# ECUs.net
KiCad netlist of a schematic drawn in EasyEDA
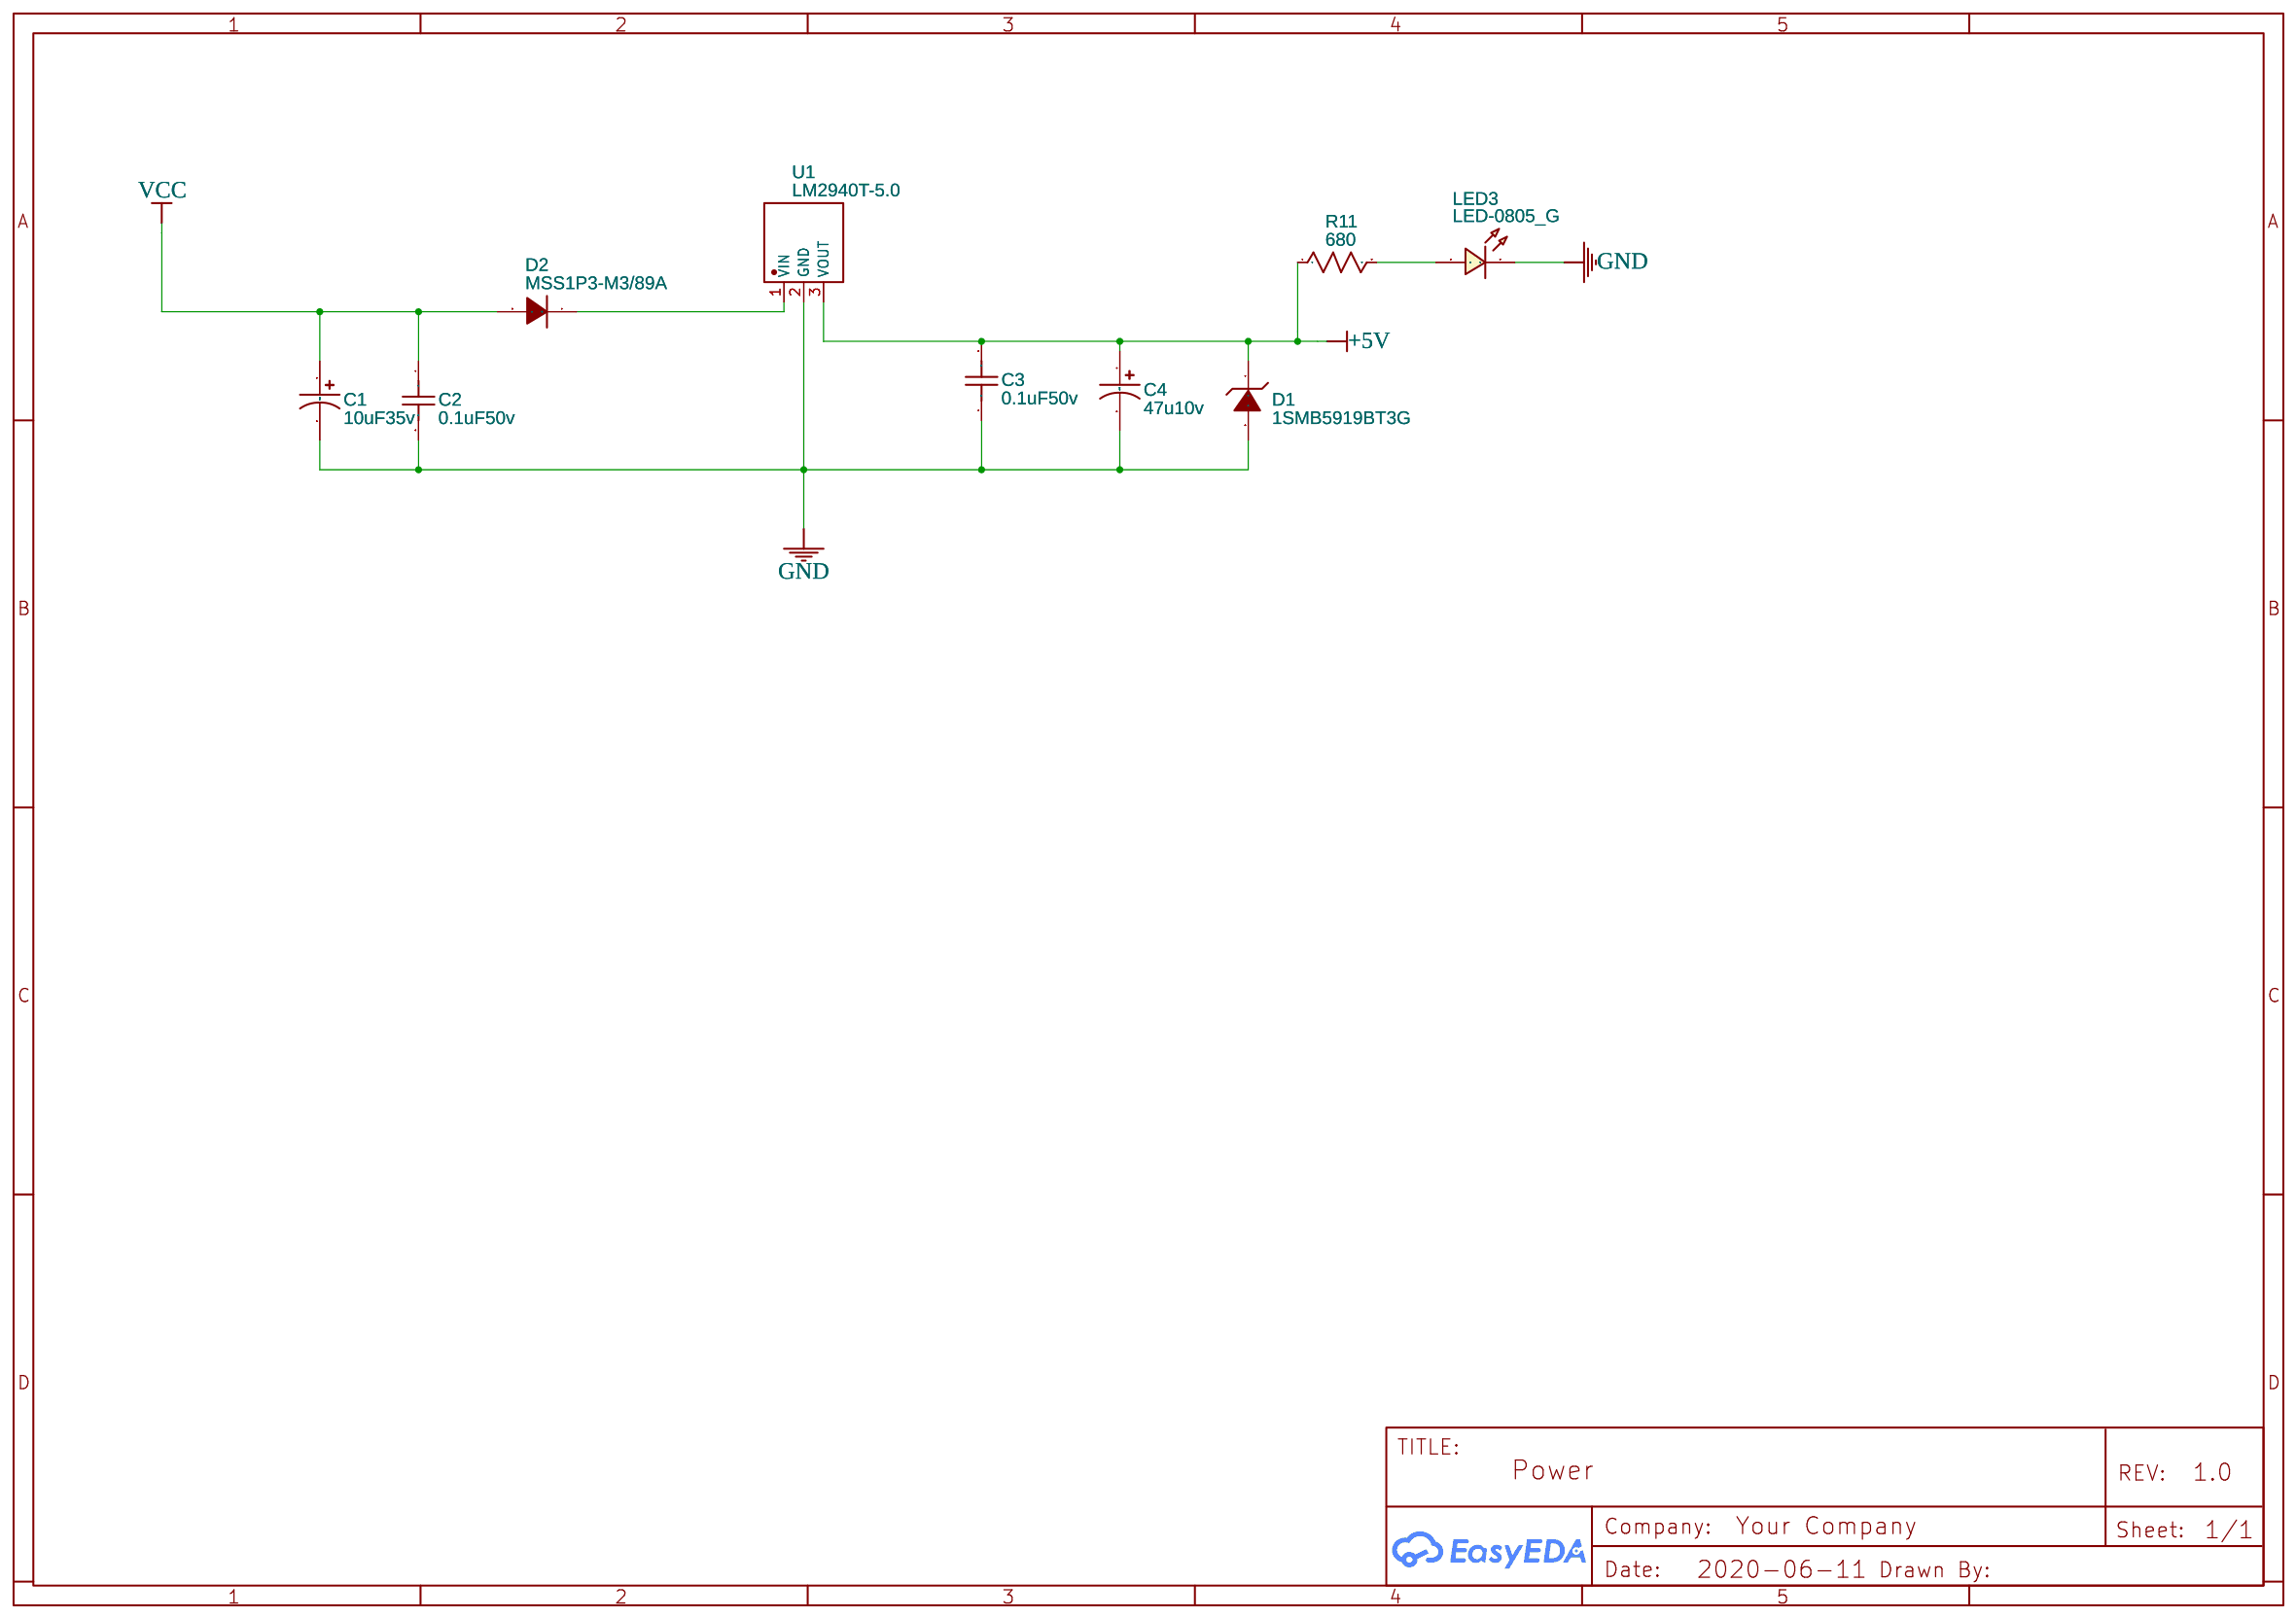
[diagram p0: power]
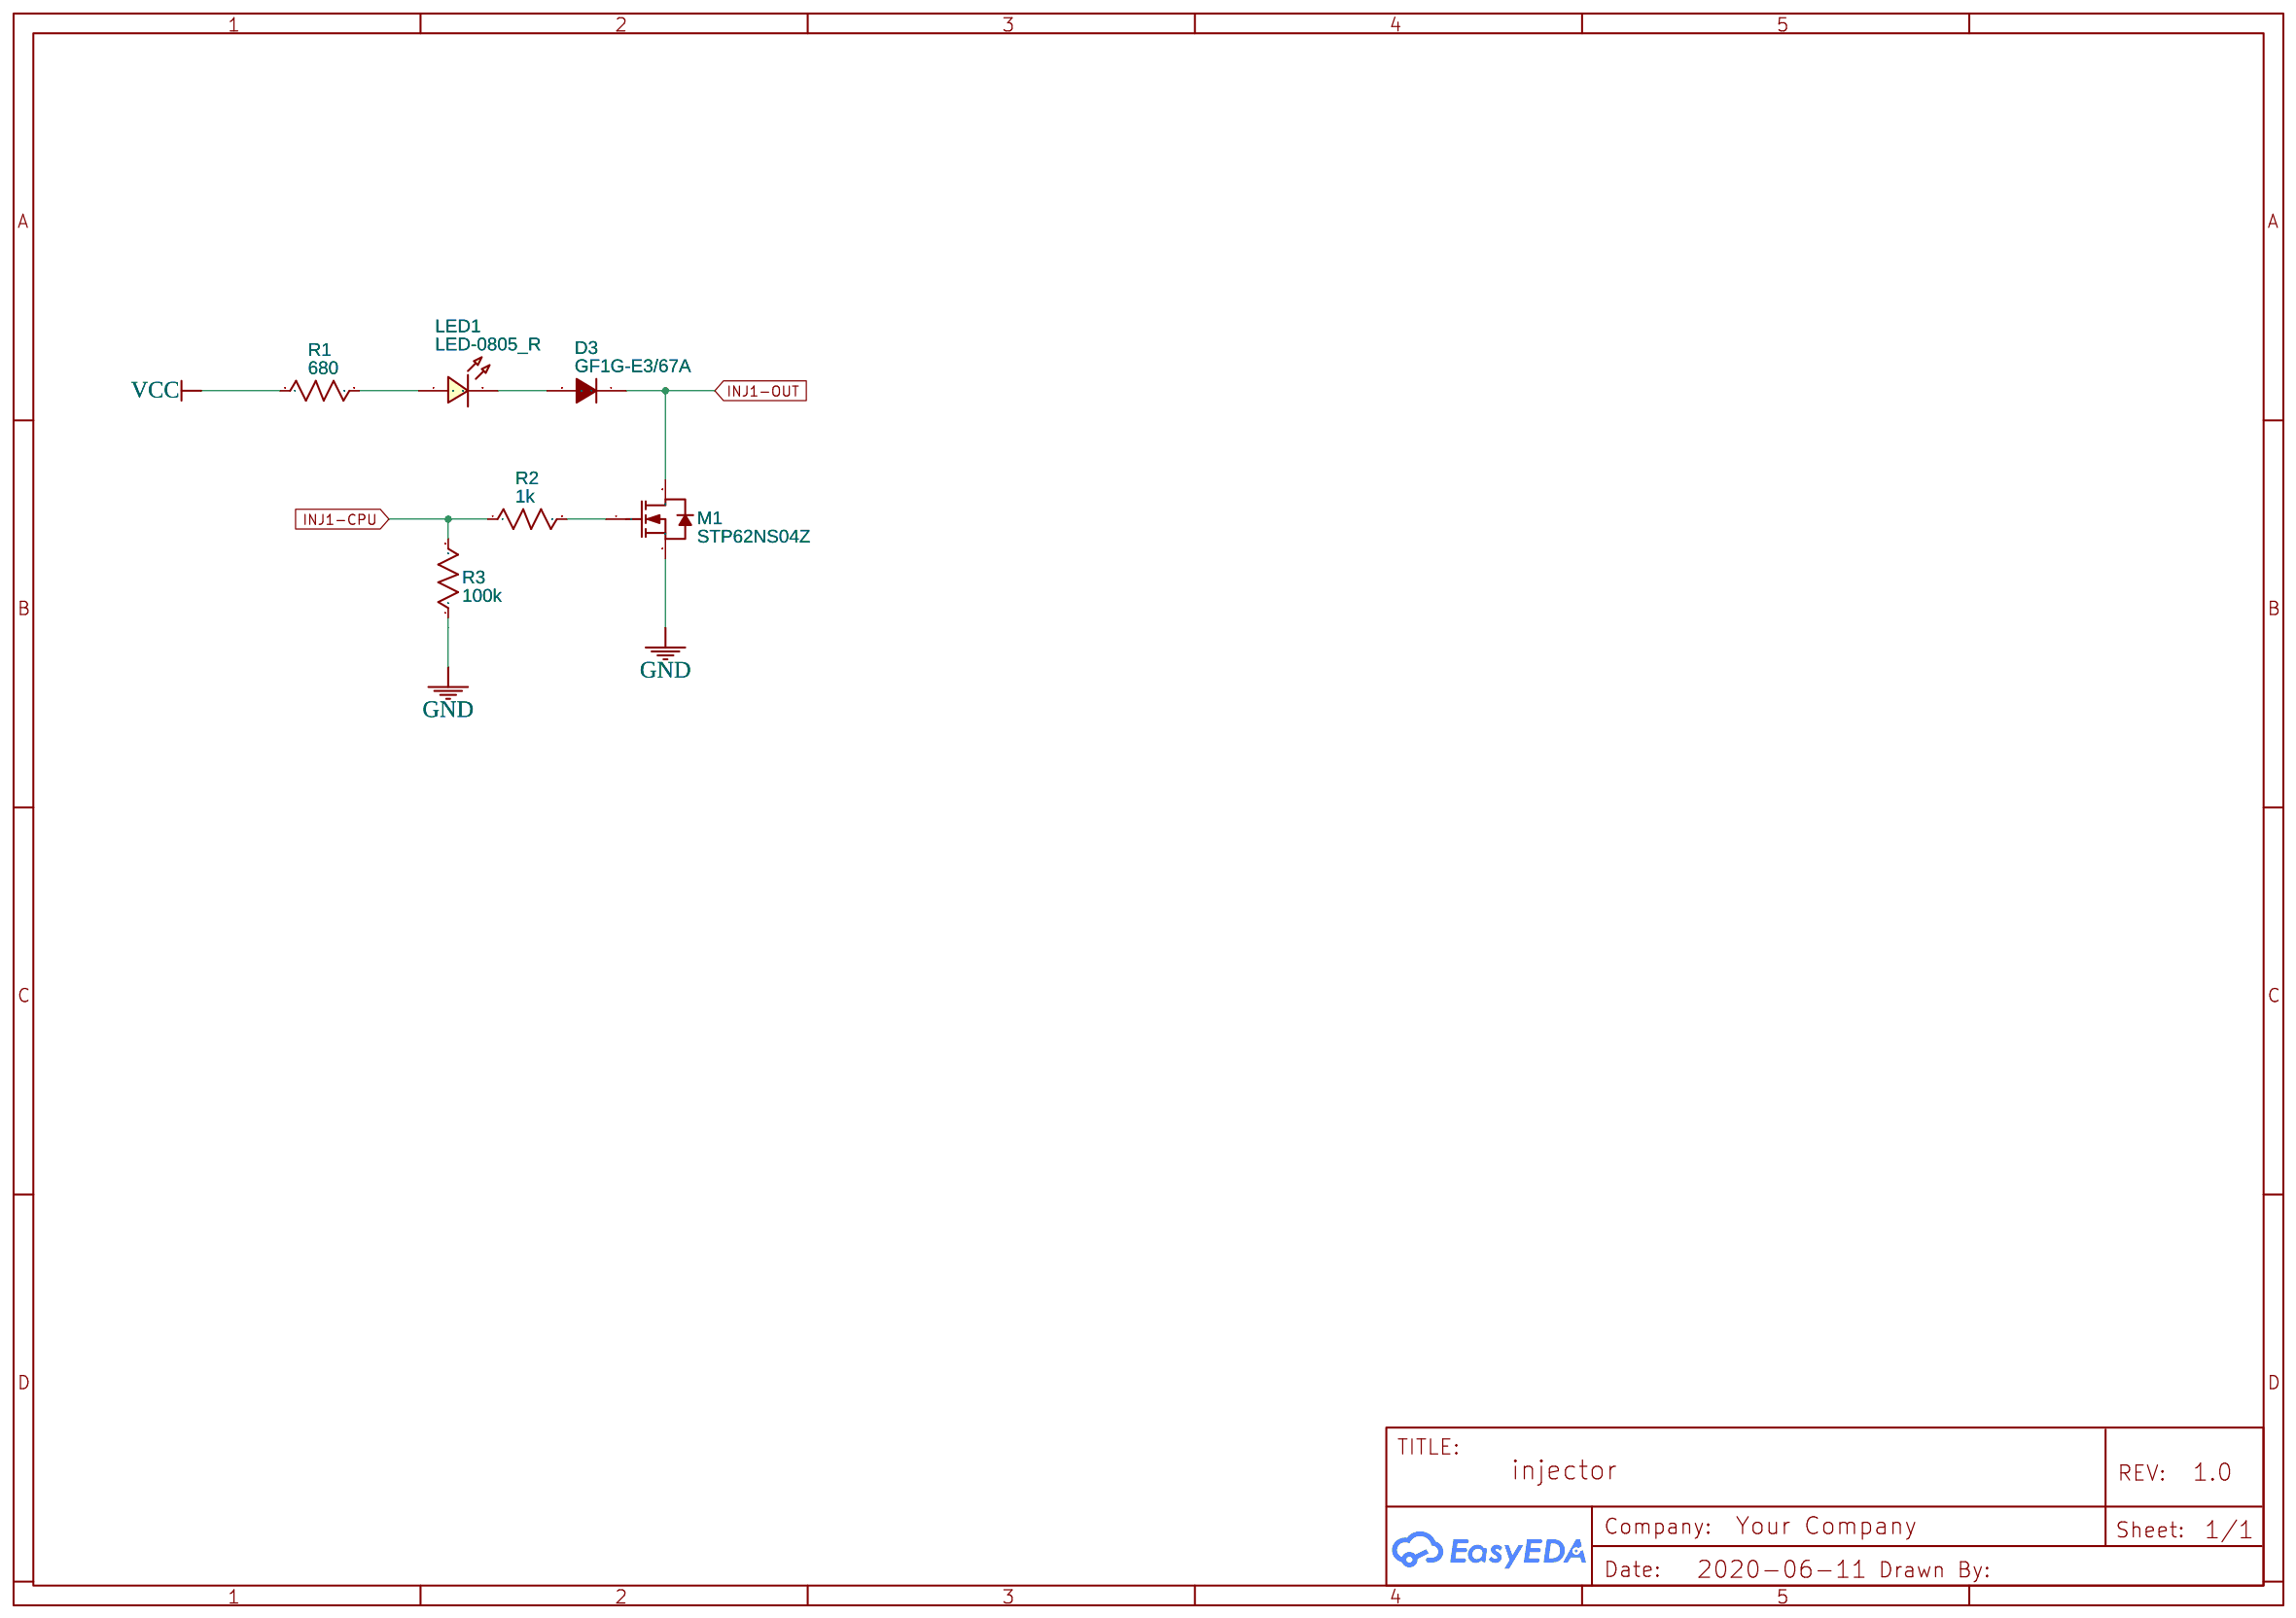
[diagram p1: INJ]
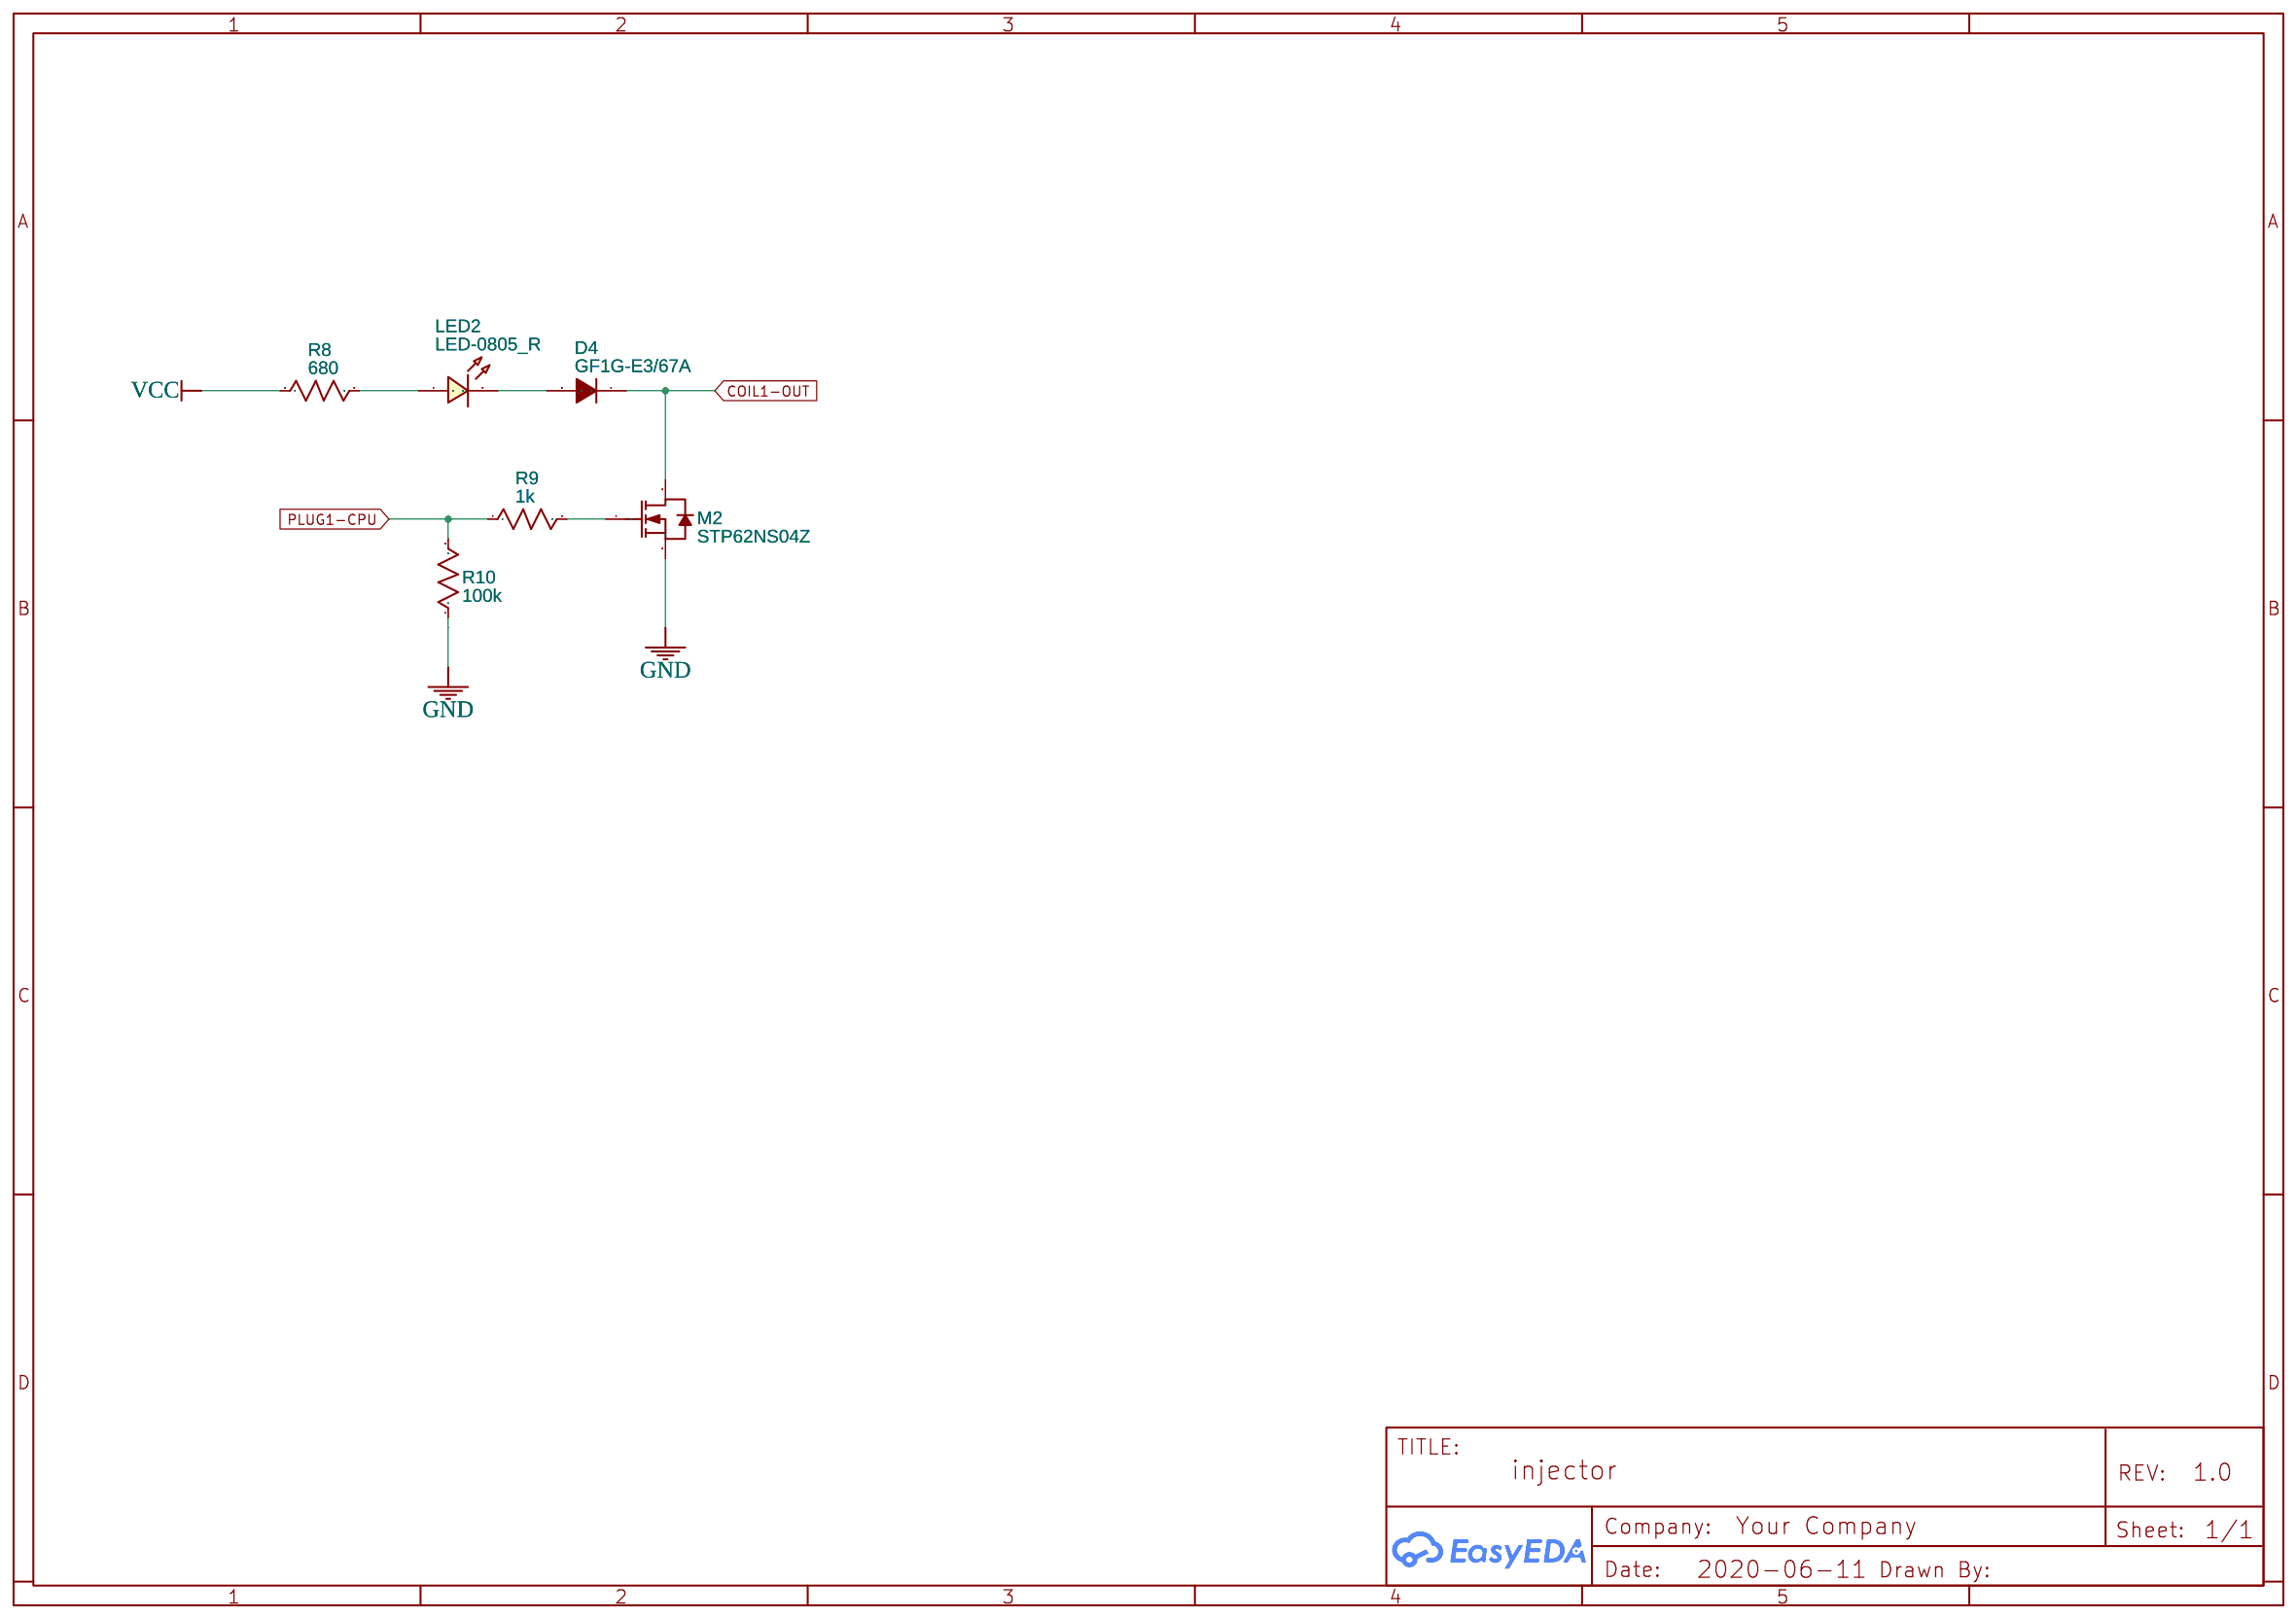
[diagram p2: plug]
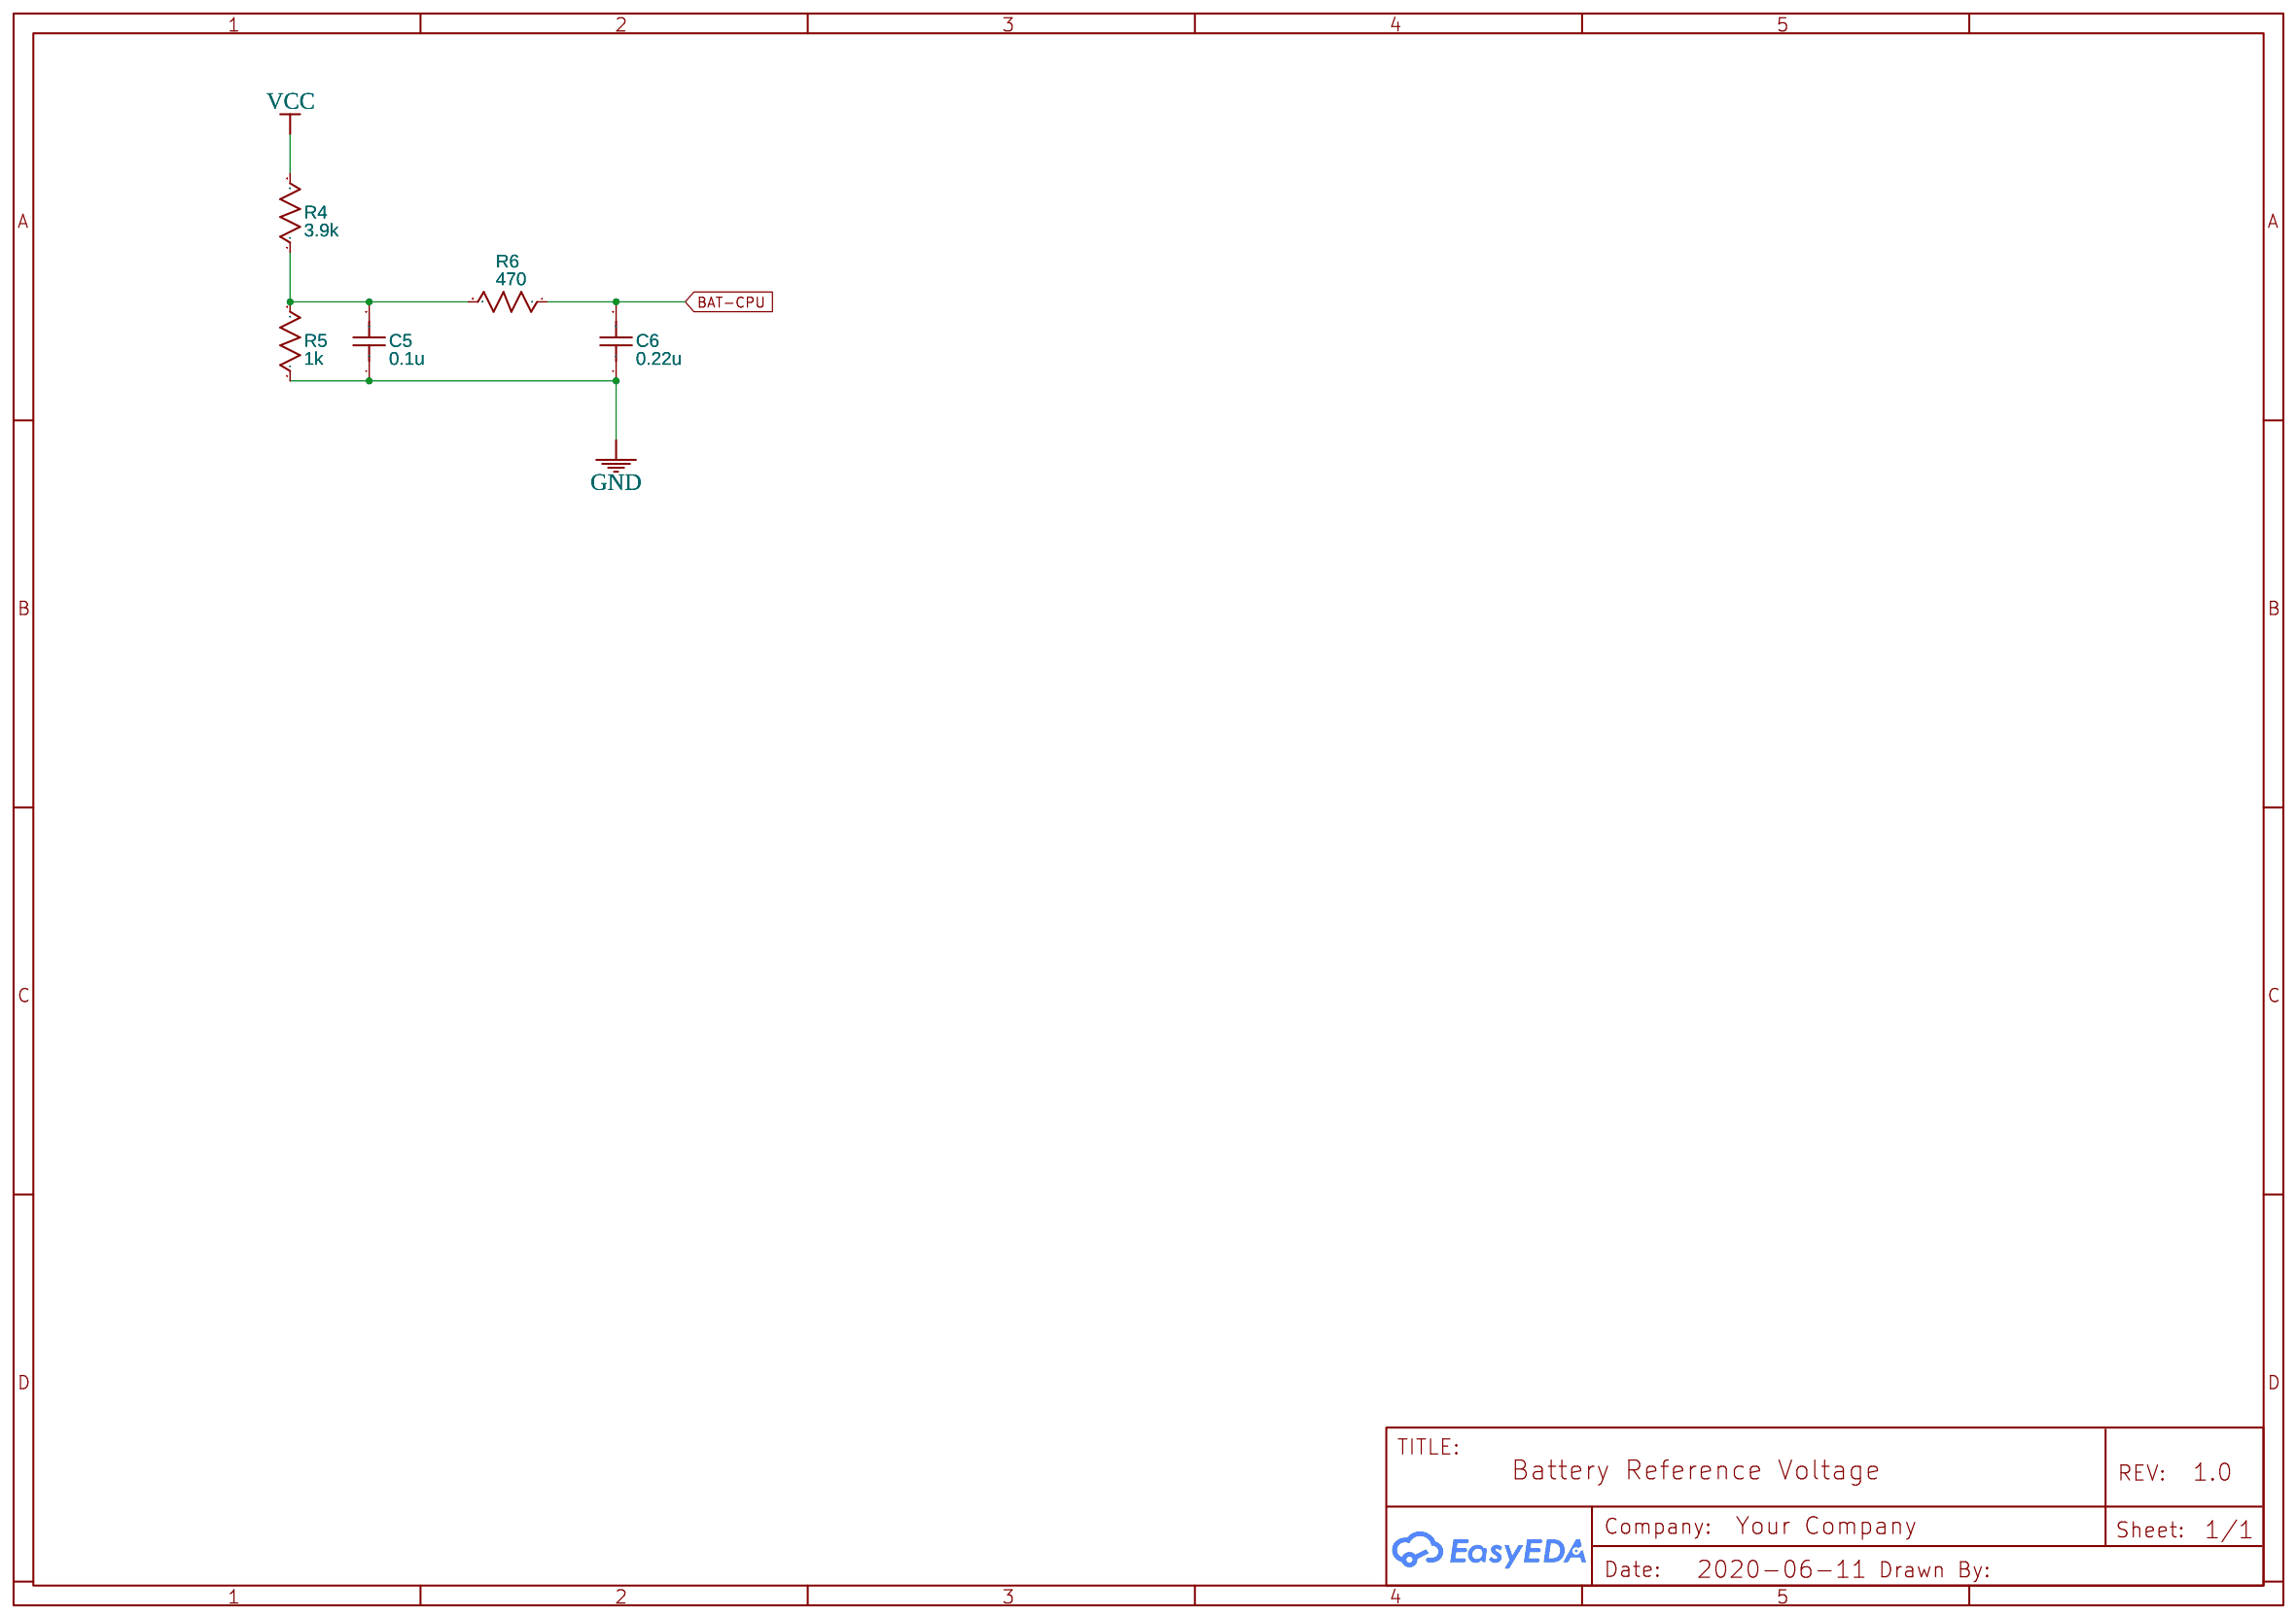
[diagram p3: Batt]
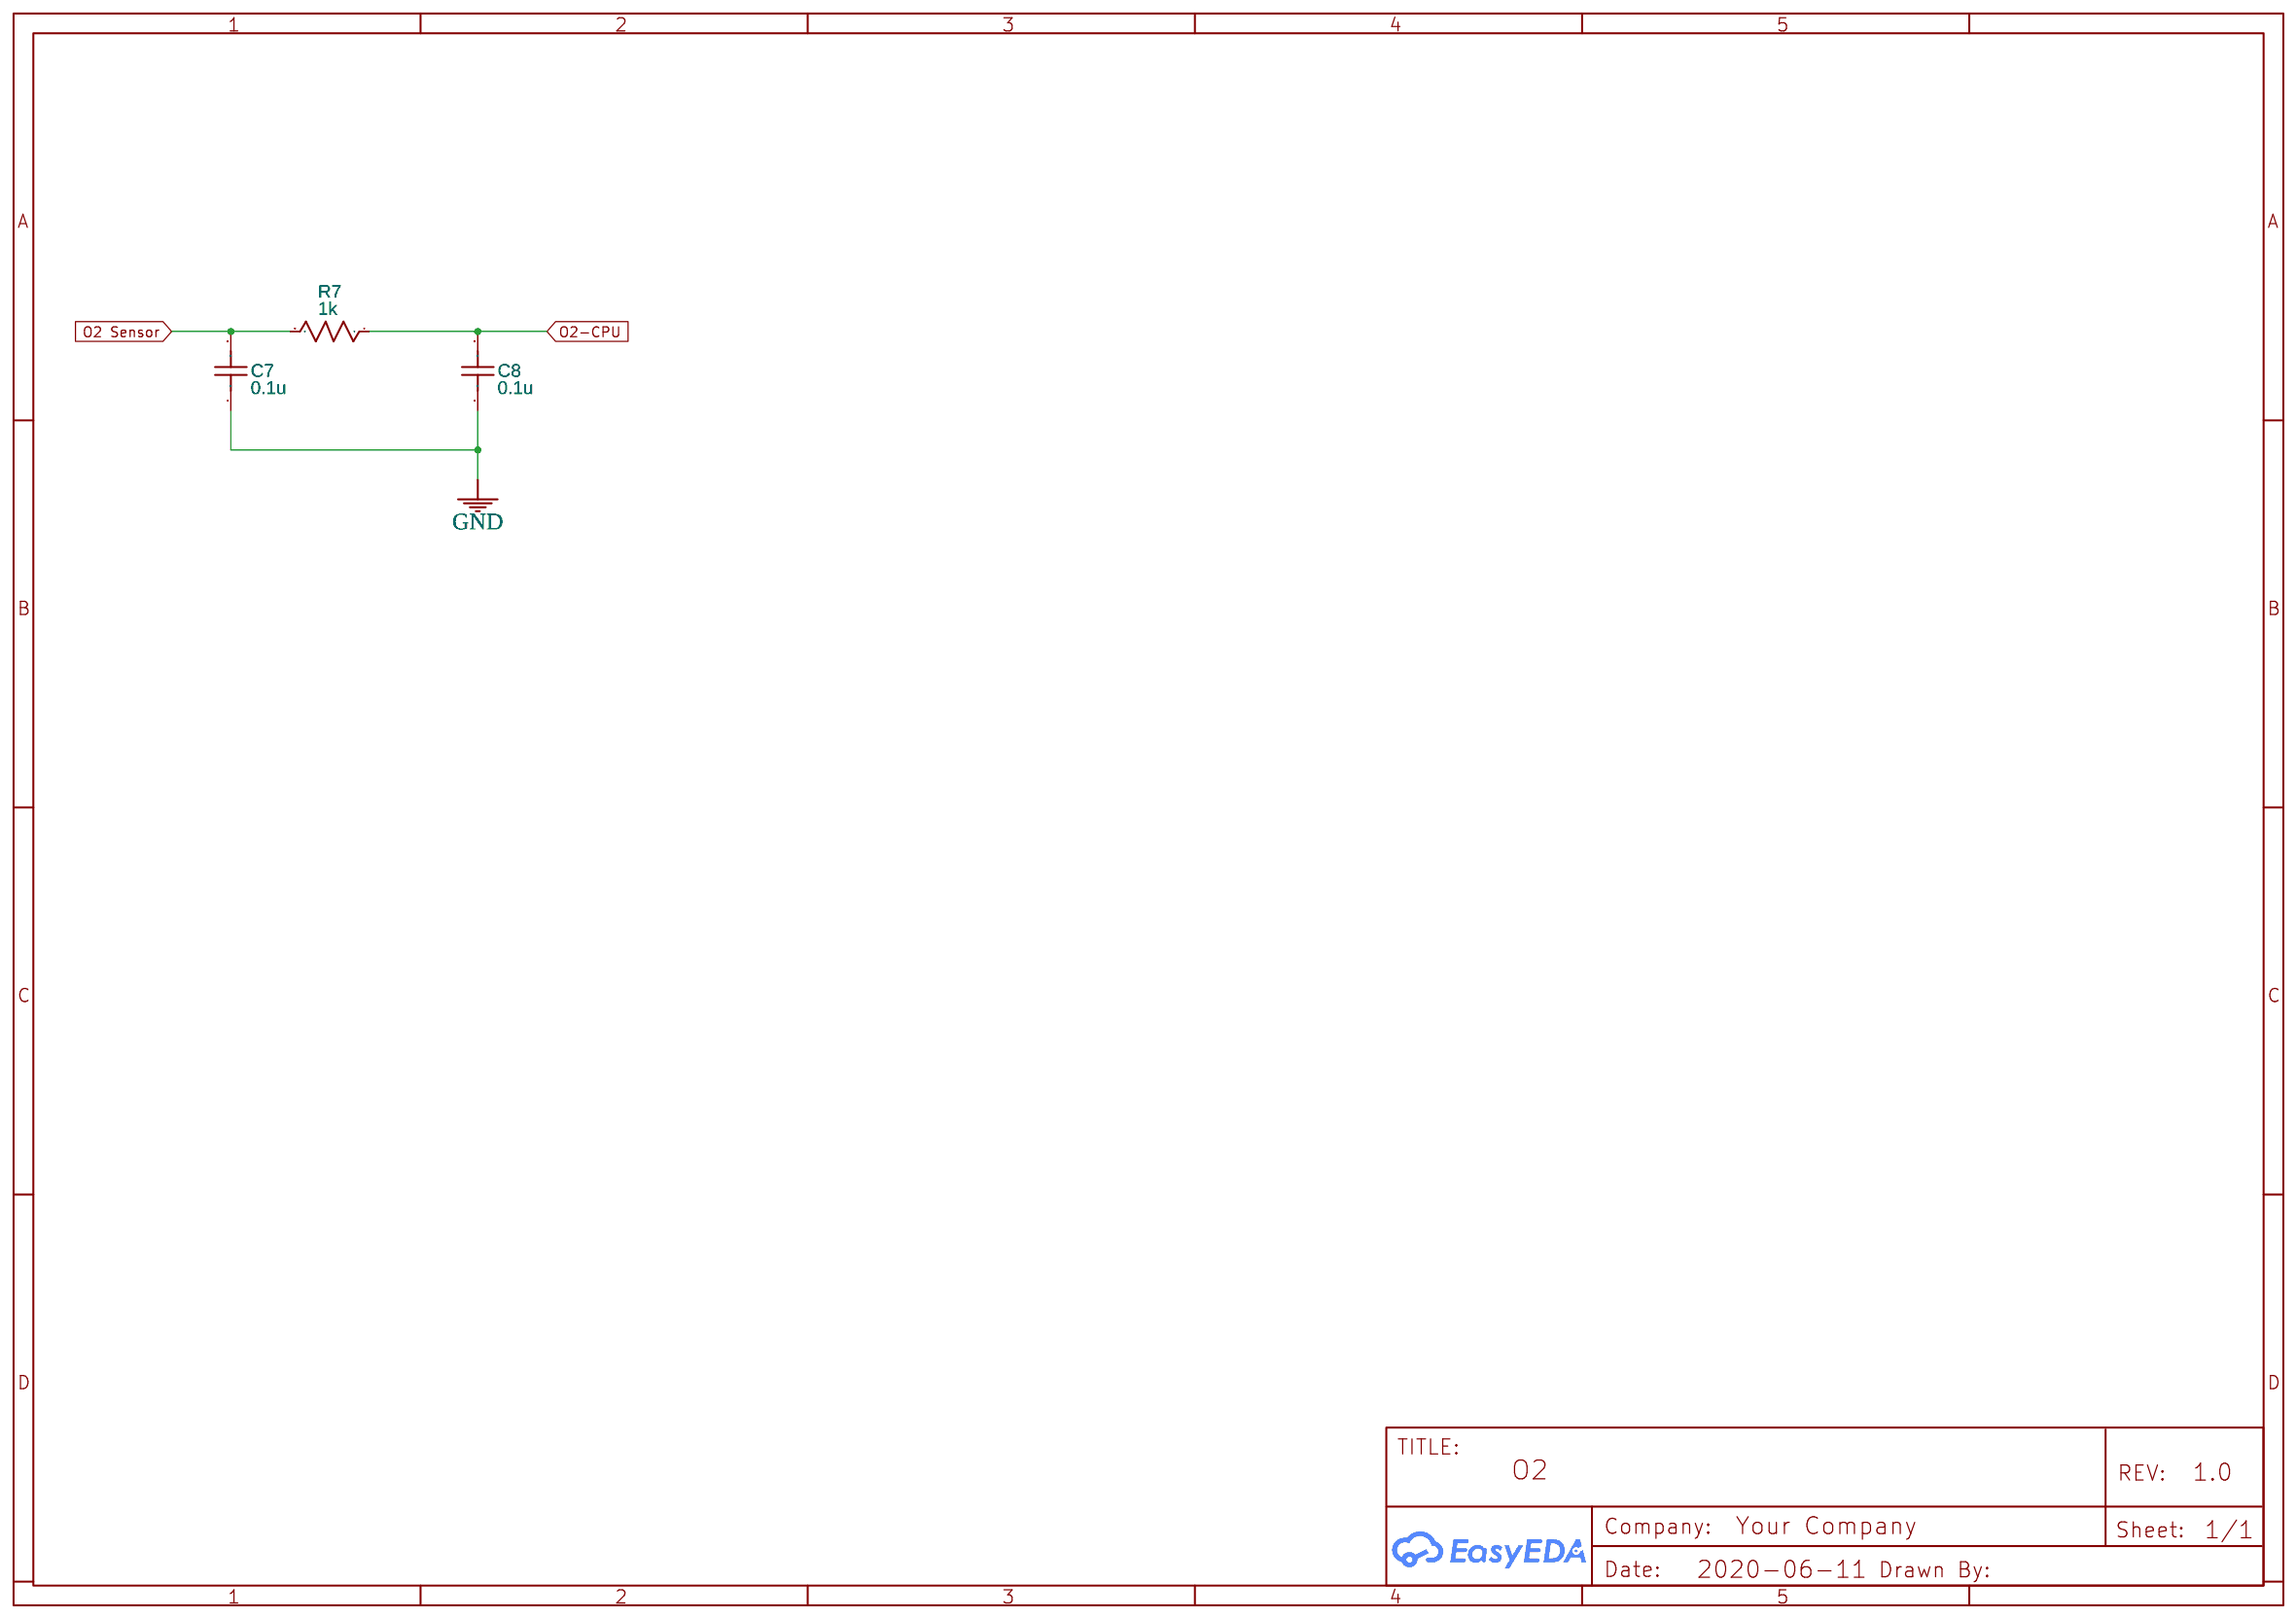
[diagram p4: O2]
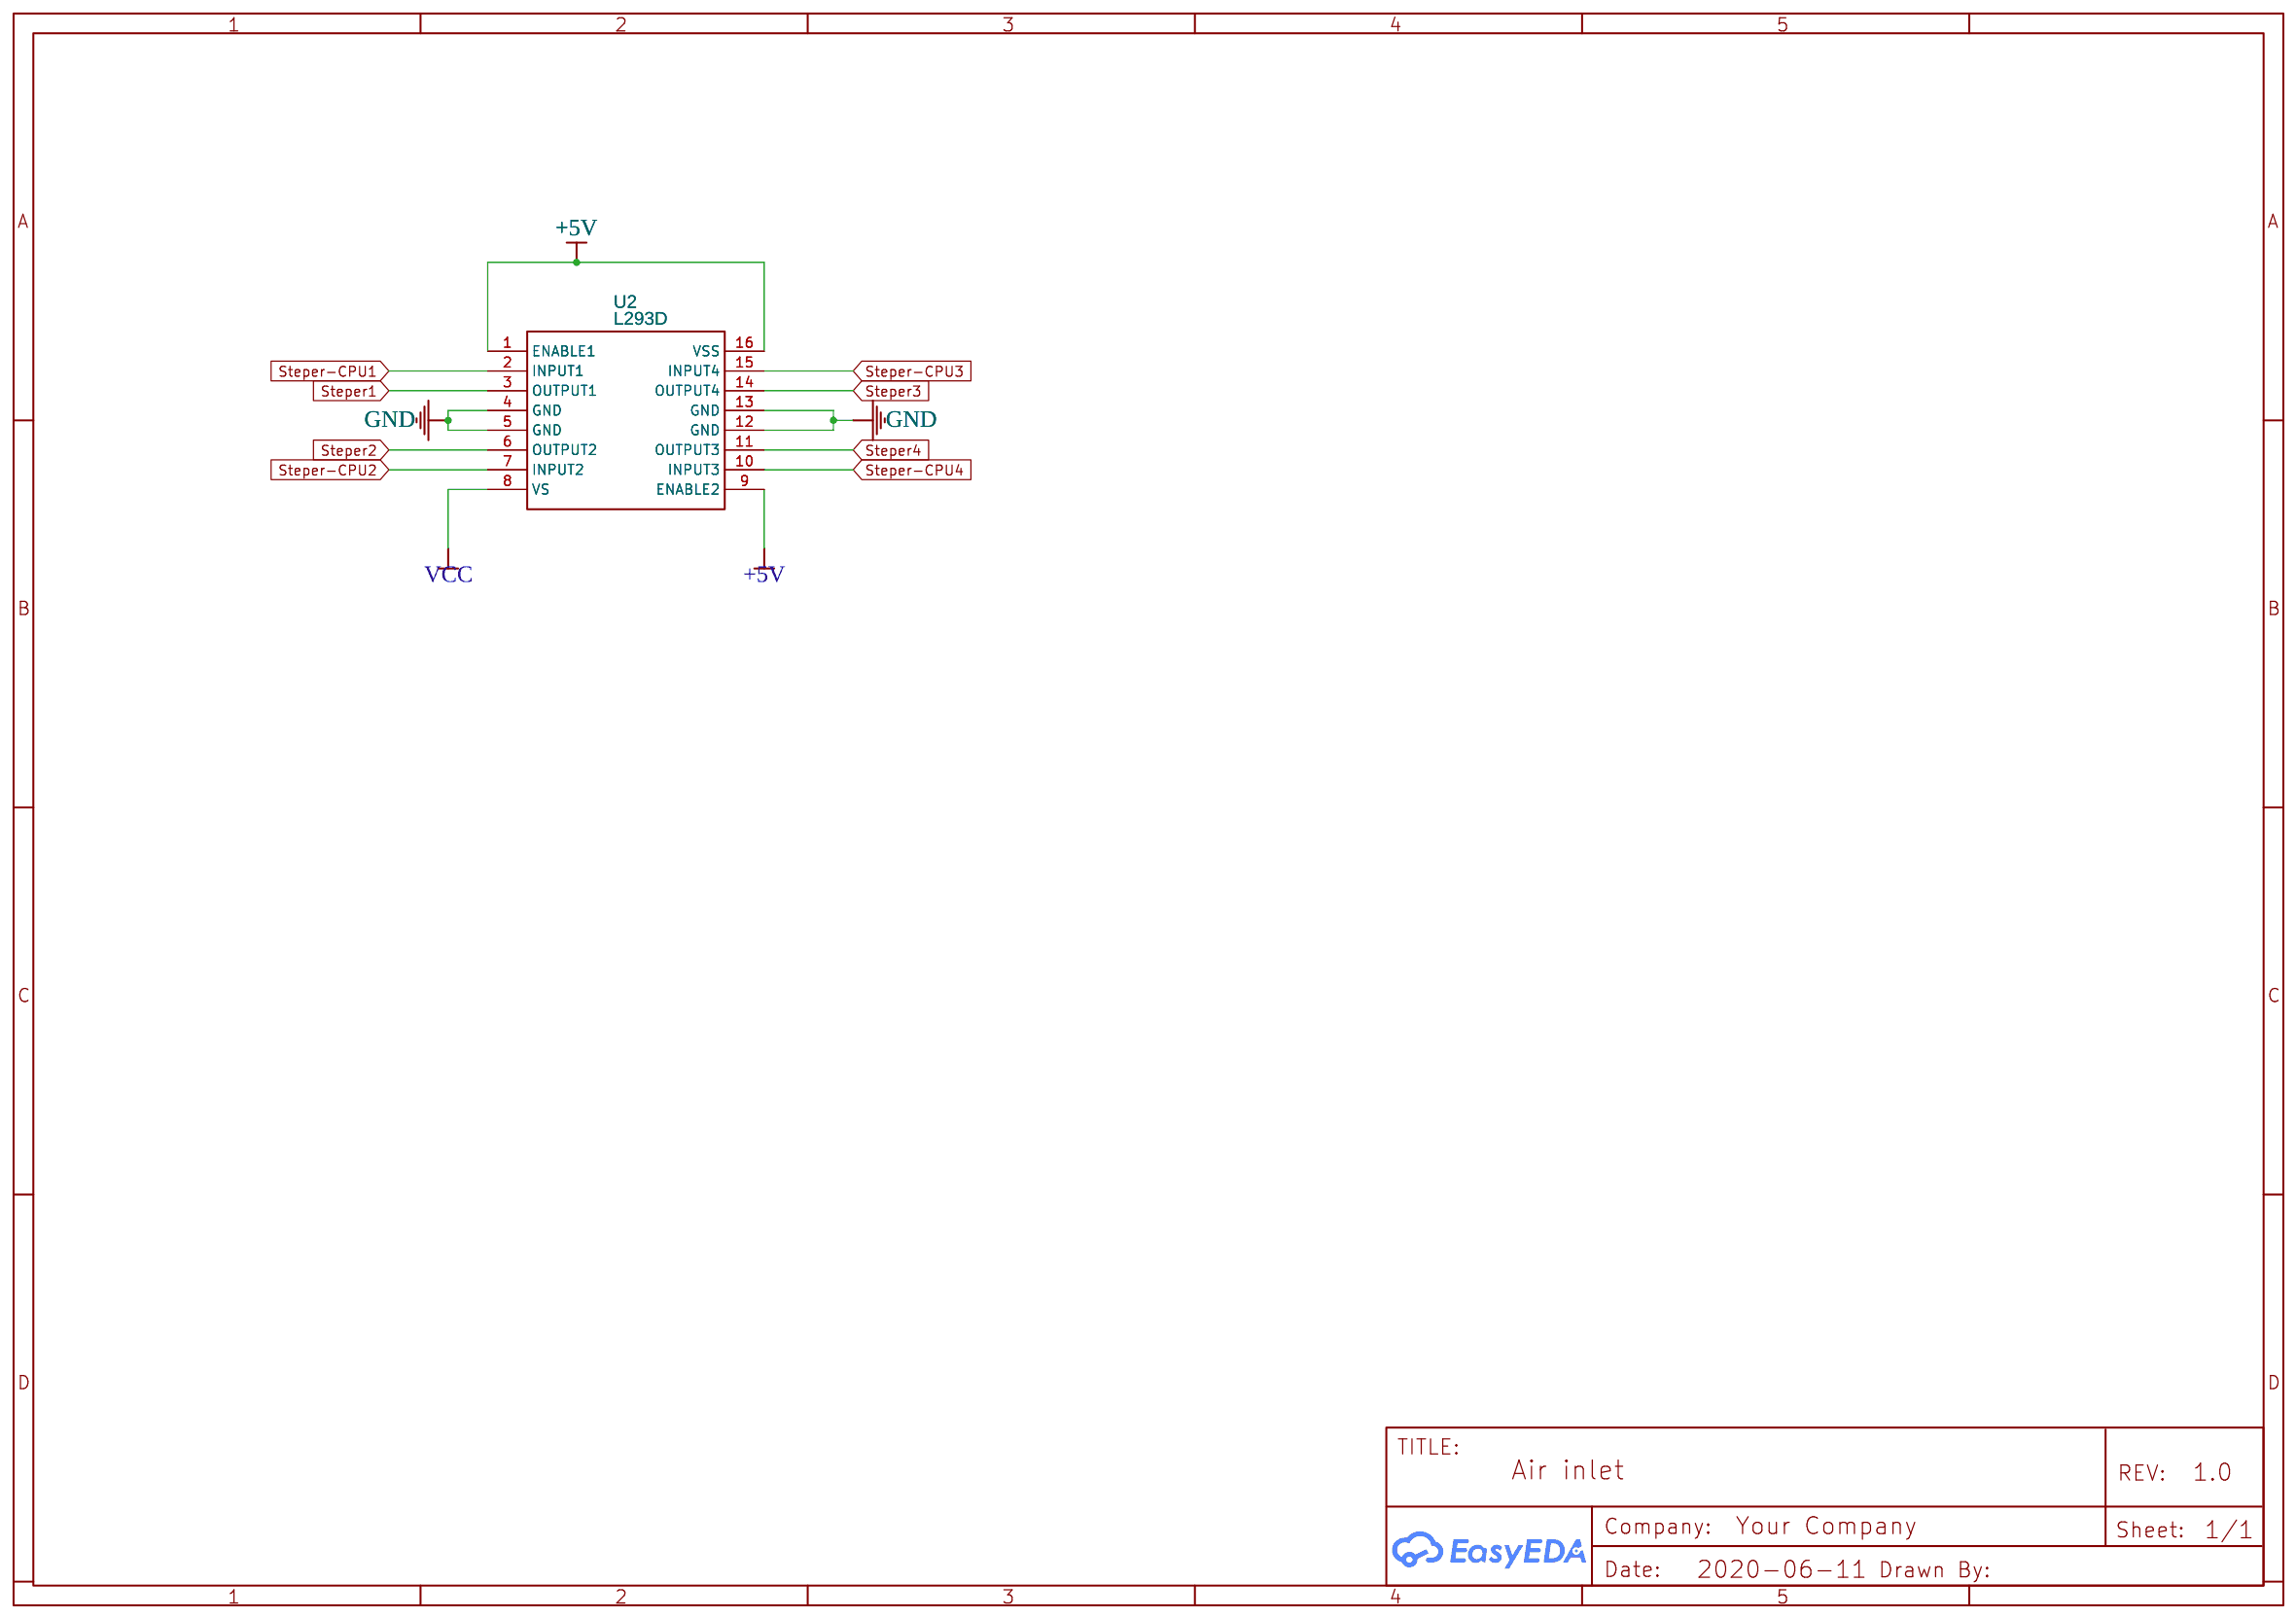
[diagram p5: AIC]
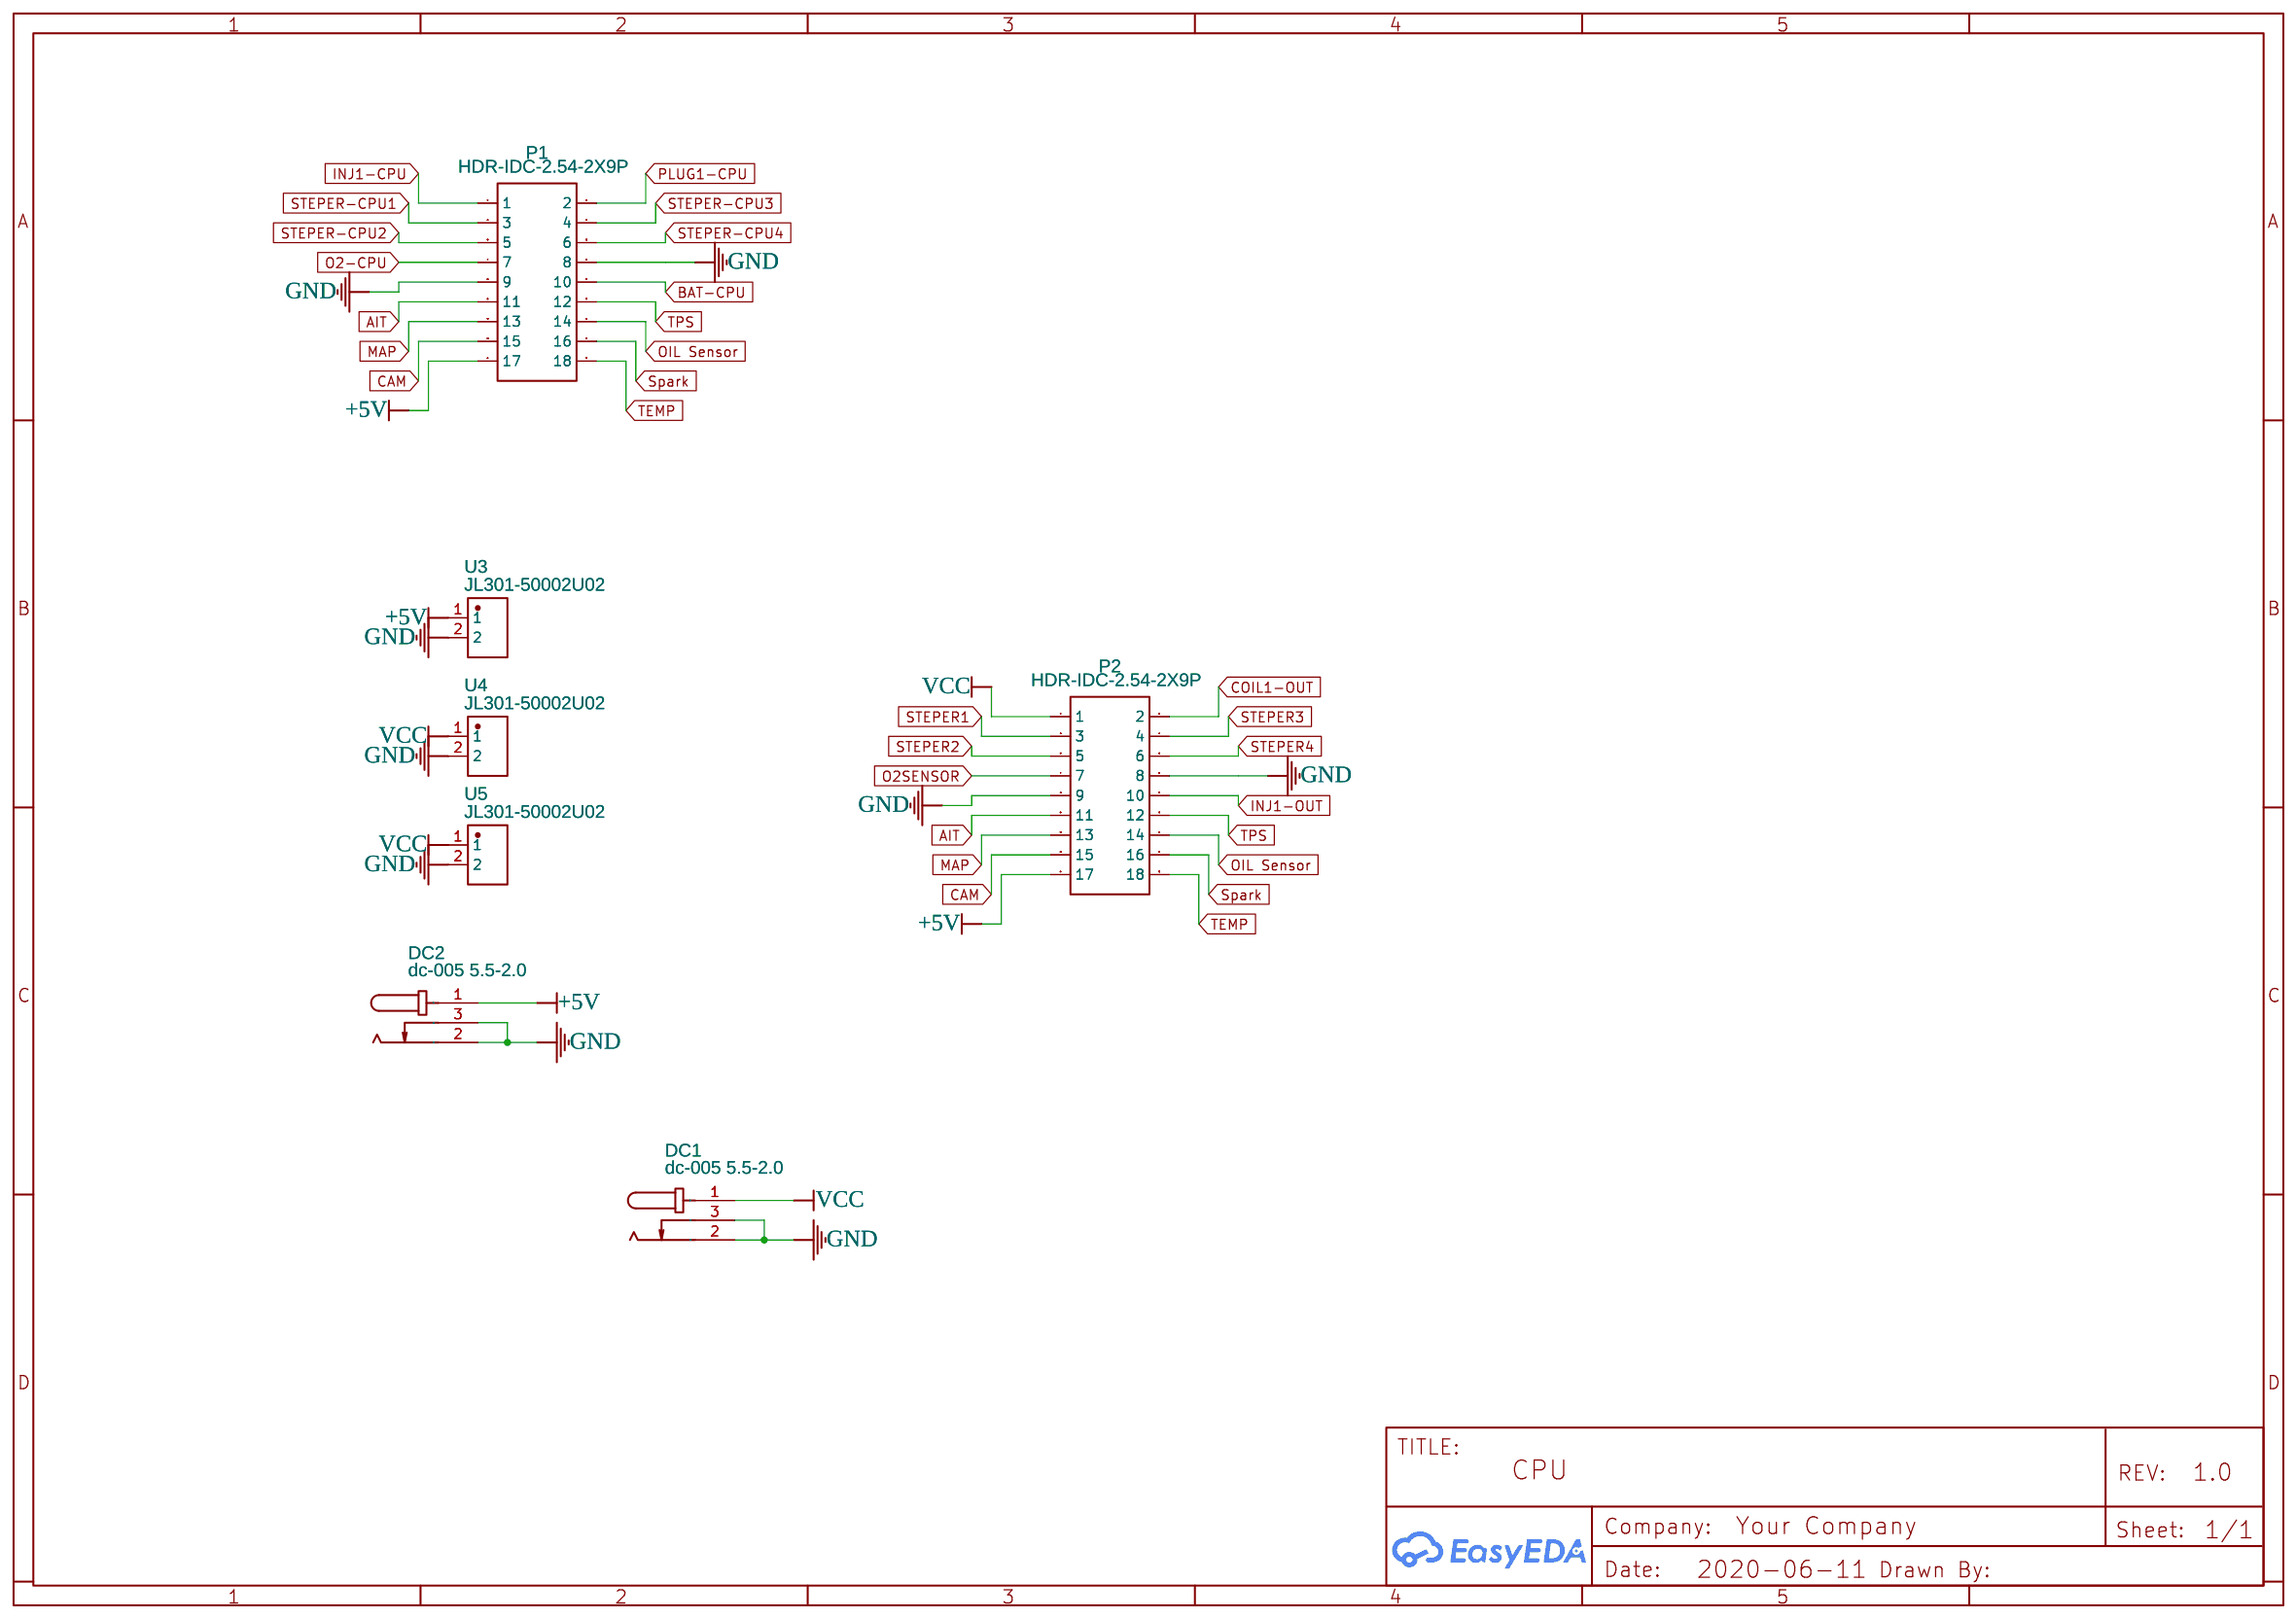
[diagram p6: CPU]

(export (version "E")
  (design (tool "Eeschema 10.0.6"))
  (components
    (comp (ref "C1")
      (value "10uF35v")
      (fields
        (field (name "BOM_Manufacturer Part") "T491C106K035AT")
        (field (name "BOM_Supplier Part") "80-T491C106K035")
      )
      (libsource (lib "") (part "C_Tan_SMD_A_US"))
    )
    (comp (ref "C2")
      (value "0.1uF50v")
      (fields
        (field (name "BOM_Manufacturer Part") "VJ1210Y104MXAAT")
        (field (name "BOM_Supplier Part") "77-VJ1210Y104MXAAT")
      )
      (libsource (lib "") (part "C_1206_US"))
    )
    (comp (ref "C3")
      (value "0.1uF50v")
      (fields
        (field (name "BOM_Manufacturer Part") "VJ1210Y104MXAAT")
        (field (name "BOM_Supplier Part") "77-VJ1210Y104MXAAT")
      )
      (libsource (lib "") (part "C_1206_US_1"))
    )
    (comp (ref "C4")
      (value "47u10v")
      (fields
        (field (name "BOM_Manufacturer Part") "T491B476K006AT")
        (field (name "BOM_Supplier Part") "80-T491B476K006")
      )
      (libsource (lib "") (part "C_Tan_SMD_B_US"))
    )
    (comp (ref "D1")
      (value "1SMB5919BT3G")
      (fields (field (name "BOM_Supplier Part") "C70260"))
      (libsource (lib "") (part "1SMB5919BT3G"))
    )
    (comp (ref "D2")
      (value "MSS1P3-M3/89A")
      (fields (field (name "BOM_Supplier Part") "C111315"))
      (libsource (lib "") (part "MSS1P3-M3/89A"))
    )
    (comp (ref "LED3")
      (value "LED-0805_G")
      (fields (field (name "BOM_Manufacturer Part") "NCD0805G1") (field (name "BOM_Supplier Part") "C84260"))
      (libsource (lib "") (part "LED-0805_G"))
    )
    (comp (ref "R11")
      (value "680")
      (fields
        (field (name "BOM_Manufacturer Part") "RT1206FRE07680RL")
        (field (name "BOM_Supplier Part") "603-RT1206FRE07680RL")
      )
      (libsource (lib "") (part "R_1206_US"))
    )
    (comp (ref "U1")
      (value "LM2940T-5.0")
      (fields (field (name "BOM_Supplier Part") "C434573"))
      (libsource (lib "") (part "LM2940T-5.0"))
    )
    (comp (ref "D3")
      (value "GF1G-E3/67A")
      (fields (field (name "BOM_Supplier Part") "C145458"))
      (libsource (lib "") (part "GF1G-E3/67A"))
    )
    (comp (ref "LED1")
      (value "LED-0805_R")
      (fields
        (field (name "BOM_Manufacturer Part") "17-21SURC/S530-A3/TR8")
        (field (name "BOM_Supplier Part") "C72037")
      )
      (libsource (lib "") (part "LED-0805_R"))
    )
    (comp (ref "M1")
      (value "STP62NS04Z")
      (fields (field (name "BOM_Supplier Part") "761-0152"))
      (libsource (lib "") (part "STP62NS04Z"))
    )
    (comp (ref "R1")
      (value "680")
      (fields
        (field (name "BOM_Manufacturer Part") "RT1206FRE07680RL")
        (field (name "BOM_Supplier Part") "603-RT1206FRE07680RL")
      )
      (libsource (lib "") (part "R_1206_US_1"))
    )
    (comp (ref "R2")
      (value "1k")
      (fields
        (field (name "BOM_Manufacturer Part") "RC1206FR-071KL")
        (field (name "BOM_Supplier Part") "C131398")
      )
      (libsource (lib "") (part "R_1206_US_1"))
    )
    (comp (ref "R3")
      (value "100k")
      (fields
        (field (name "BOM_Manufacturer Part") "RC1206FR-07100KL")
        (field (name "BOM_Supplier Part") "C137393")
      )
      (libsource (lib "") (part "R_1206_US"))
    )
    (comp (ref "D4")
      (value "GF1G-E3/67A")
      (fields (field (name "BOM_Supplier Part") "C145458"))
      (libsource (lib "") (part "GF1G-E3/67A"))
    )
    (comp (ref "LED2")
      (value "LED-0805_R")
      (fields
        (field (name "BOM_Manufacturer Part") "17-21SURC/S530-A3/TR8")
        (field (name "BOM_Supplier Part") "C72037")
      )
      (libsource (lib "") (part "LED-0805_R"))
    )
    (comp (ref "M2")
      (value "STP62NS04Z")
      (fields (field (name "BOM_Supplier Part") "761-0152"))
      (libsource (lib "") (part "STP62NS04Z"))
    )
    (comp (ref "R8")
      (value "680")
      (fields
        (field (name "BOM_Manufacturer Part") "RT1206FRE07680RL")
        (field (name "BOM_Supplier Part") "603-RT1206FRE07680RL")
      )
      (libsource (lib "") (part "R_1206_US"))
    )
    (comp (ref "R9")
      (value "1k")
      (fields
        (field (name "BOM_Manufacturer Part") "RC1206FR-071KL")
        (field (name "BOM_Supplier Part") "C131398")
      )
      (libsource (lib "") (part "R_1206_US"))
    )
    (comp (ref "R10")
      (value "100k")
      (fields
        (field (name "BOM_Manufacturer Part") "RC1206FR-07100KL")
        (field (name "BOM_Supplier Part") "C137393")
      )
      (libsource (lib "") (part "R_1206_US_1"))
    )
    (comp (ref "C5")
      (value "0.1u")
      (fields
        (field (name "BOM_Manufacturer Part") "T491A104M050AT")
        (field (name "BOM_Supplier Part") "80-T491A104M050AT")
      )
      (libsource (lib "") (part "C_1206_US"))
    )
    (comp (ref "C6")
      (value "0.22u")
      (fields
        (field (name "BOM_Manufacturer Part") "TPSA224K050R7000")
        (field (name "BOM_Supplier Part") "581-TPSA224K050R7000")
      )
      (libsource (lib "") (part "C_1206_US"))
    )
    (comp (ref "R4")
      (value "3.9k")
      (fields
        (field (name "BOM_Manufacturer Part") "RC1206FR-073R9L")
        (field (name "BOM_Supplier Part") "C137280")
      )
      (libsource (lib "") (part "R_1206_US"))
    )
    (comp (ref "R5")
      (value "1k")
      (fields
        (field (name "BOM_Manufacturer Part") "RC1206FR-071KL")
        (field (name "BOM_Supplier Part") "C131398")
      )
      (libsource (lib "") (part "R_1206_US"))
    )
    (comp (ref "R6")
      (value "470")
      (fields
        (field (name "BOM_Manufacturer Part") "RC1206FR-07470RL")
        (field (name "BOM_Supplier Part") "C114945")
      )
      (libsource (lib "") (part "R_1206_US_1"))
    )
    (comp (ref "C7")
      (value "0.1u")
      (fields
        (field (name "BOM_Manufacturer Part") "T491A104M050AT")
        (field (name "BOM_Supplier Part") "80-T491A104M050AT")
      )
      (libsource (lib "") (part "C_1206_US"))
    )
    (comp (ref "C8")
      (value "0.1u")
      (fields
        (field (name "BOM_Manufacturer Part") "T491A104M050AT")
        (field (name "BOM_Supplier Part") "80-T491A104M050AT")
      )
      (libsource (lib "") (part "C_1206_US"))
    )
    (comp (ref "R7")
      (value "1k")
      (fields
        (field (name "BOM_Manufacturer Part") "RC1206FR-071KL")
        (field (name "BOM_Supplier Part") "C131398")
      )
      (libsource (lib "") (part "R_1206_US"))
    )
    (comp (ref "U2")
      (value "L293D")
      (fields (field (name "BOM_Supplier Part") "C12340"))
      (libsource (lib "") (part "L293D"))
    )
    (comp (ref "DC1")
      (value "dc-005 5.5-2.0")
      (fields (field (name "BOM_Supplier Part") "C132516"))
      (libsource (lib "") (part "dc-005 5.5-2.0"))
    )
    (comp (ref "DC2")
      (value "dc-005 5.5-2.0")
      (fields (field (name "BOM_Supplier Part") "C132516"))
      (libsource (lib "") (part "dc-005 5.5-2.0"))
    )
    (comp (ref "P1")
      (value "HDR-IDC-2.54-2X9P")
      (fields
        (field (name "BOM_Manufacturer Part") "2X9 2.54mm IDC Box")
        (field (name "BOM_Supplier Part") "C11216")
      )
      (libsource (lib "") (part "HDR-IDC-2.54-2X9P"))
    )
    (comp (ref "P2")
      (value "HDR-IDC-2.54-2X9P")
      (fields
        (field (name "BOM_Manufacturer Part") "2X9 2.54mm IDC Box")
        (field (name "BOM_Supplier Part") "C11216")
      )
      (libsource (lib "") (part "HDR-IDC-2.54-2X9P"))
    )
    (comp (ref "U3")
      (value "JL301-50002U02")
      (fields (field (name "BOM_Supplier Part") "C395214"))
      (libsource (lib "") (part "JL301-50002U02"))
    )
    (comp (ref "U4")
      (value "JL301-50002U02")
      (fields (field (name "BOM_Supplier Part") "C395214"))
      (libsource (lib "") (part "JL301-50002U02"))
    )
    (comp (ref "U5")
      (value "JL301-50002U02")
      (fields (field (name "BOM_Supplier Part") "C395214"))
      (libsource (lib "") (part "JL301-50002U02"))
    )
  )
  (nets
    (net (code "1") (name "+5V") (class "Default")
      (node (ref "C3") (pin "2") (pinfunction "2_2") (pintype "unspecified"))
      (node (ref "C4") (pin "1") (pinfunction "1_1") (pintype "unspecified"))
      (node (ref "D1") (pin "1") (pinfunction "K_1") (pintype "unspecified"))
      (node (ref "DC2") (pin "1") (pinfunction "1_1") (pintype "unspecified"))
      (node (ref "P1") (pin "17") (pinfunction "17_17") (pintype "unspecified"))
      (node (ref "P2") (pin "17") (pinfunction "17_17") (pintype "unspecified"))
      (node (ref "R11") (pin "1") (pinfunction "1_1") (pintype "unspecified"))
      (node (ref "U1") (pin "3") (pinfunction "VOUT_3") (pintype "unspecified"))
      (node (ref "U2") (pin "1") (pinfunction "ENABLE1_1") (pintype "unspecified"))
      (node (ref "U2") (pin "16") (pinfunction "VSS_16") (pintype "unspecified"))
      (node (ref "U2") (pin "9") (pinfunction "ENABLE2_9") (pintype "unspecified"))
      (node (ref "U3") (pin "1") (pinfunction "1_1") (pintype "unspecified"))
    )
    (net (code "2") (name "AIT") (class "Default")
      (node (ref "P1") (pin "11") (pinfunction "11_11") (pintype "unspecified"))
      (node (ref "P2") (pin "11") (pinfunction "11_11") (pintype "unspecified"))
    )
    (net (code "3") (name "BAT-CPU") (class "Default")
      (node (ref "C6") (pin "2") (pinfunction "2_2") (pintype "unspecified"))
      (node (ref "P1") (pin "10") (pinfunction "10_10") (pintype "unspecified"))
      (node (ref "R6") (pin "1") (pinfunction "1_1") (pintype "unspecified"))
    )
    (net (code "4") (name "CAM") (class "Default")
      (node (ref "P1") (pin "15") (pinfunction "15_15") (pintype "unspecified"))
      (node (ref "P2") (pin "15") (pinfunction "15_15") (pintype "unspecified"))
    )
    (net (code "5") (name "COIL1-OUT") (class "Default")
      (node (ref "D4") (pin "1") (pinfunction "K_1") (pintype "unspecified"))
      (node (ref "M2") (pin "2") (pinfunction "D_2") (pintype "unspecified"))
      (node (ref "P2") (pin "2") (pinfunction "2_2") (pintype "unspecified"))
    )
    (net (code "6") (name "GND") (class "Default")
      (node (ref "C1") (pin "2") (pinfunction "2_2") (pintype "unspecified"))
      (node (ref "C2") (pin "2") (pinfunction "2_2") (pintype "unspecified"))
      (node (ref "C3") (pin "1") (pinfunction "1_1") (pintype "unspecified"))
      (node (ref "C4") (pin "2") (pinfunction "2_2") (pintype "unspecified"))
      (node (ref "C5") (pin "1") (pinfunction "1_1") (pintype "unspecified"))
      (node (ref "C6") (pin "1") (pinfunction "1_1") (pintype "unspecified"))
      (node (ref "C7") (pin "1") (pinfunction "1_1") (pintype "unspecified"))
      (node (ref "C8") (pin "1") (pinfunction "1_1") (pintype "unspecified"))
      (node (ref "D1") (pin "2") (pinfunction "A_2") (pintype "unspecified"))
      (node (ref "DC1") (pin "2") (pinfunction "2_2") (pintype "unspecified"))
      (node (ref "DC1") (pin "3") (pinfunction "3_3") (pintype "unspecified"))
      (node (ref "DC2") (pin "2") (pinfunction "2_2") (pintype "unspecified"))
      (node (ref "DC2") (pin "3") (pinfunction "3_3") (pintype "unspecified"))
      (node (ref "LED3") (pin "2") (pinfunction "2_2") (pintype "unspecified"))
      (node (ref "M1") (pin "3") (pinfunction "S_3") (pintype "unspecified"))
      (node (ref "M2") (pin "3") (pinfunction "S_3") (pintype "unspecified"))
      (node (ref "P1") (pin "8") (pinfunction "8_8") (pintype "unspecified"))
      (node (ref "P1") (pin "9") (pinfunction "9_9") (pintype "unspecified"))
      (node (ref "P2") (pin "8") (pinfunction "8_8") (pintype "unspecified"))
      (node (ref "P2") (pin "9") (pinfunction "9_9") (pintype "unspecified"))
      (node (ref "R10") (pin "1") (pinfunction "1_1") (pintype "unspecified"))
      (node (ref "R3") (pin "1") (pinfunction "1_1") (pintype "unspecified"))
      (node (ref "R5") (pin "1") (pinfunction "1_1") (pintype "unspecified"))
      (node (ref "U1") (pin "2") (pinfunction "GND_2") (pintype "unspecified"))
      (node (ref "U2") (pin "12") (pinfunction "GND_12") (pintype "unspecified"))
      (node (ref "U2") (pin "13") (pinfunction "GND_13") (pintype "unspecified"))
      (node (ref "U2") (pin "4") (pinfunction "GND_4") (pintype "unspecified"))
      (node (ref "U2") (pin "5") (pinfunction "GND_5") (pintype "unspecified"))
      (node (ref "U3") (pin "2") (pinfunction "2_2") (pintype "unspecified"))
      (node (ref "U4") (pin "2") (pinfunction "2_2") (pintype "unspecified"))
      (node (ref "U5") (pin "2") (pinfunction "2_2") (pintype "unspecified"))
    )
    (net (code "7") (name "INJ1-CPU") (class "Default")
      (node (ref "P1") (pin "1") (pinfunction "1_1") (pintype "unspecified"))
      (node (ref "R2") (pin "1") (pinfunction "1_1") (pintype "unspecified"))
      (node (ref "R3") (pin "2") (pinfunction "2_2") (pintype "unspecified"))
    )
    (net (code "8") (name "INJ1-OUT") (class "Default")
      (node (ref "D3") (pin "1") (pinfunction "K_1") (pintype "unspecified"))
      (node (ref "M1") (pin "2") (pinfunction "D_2") (pintype "unspecified"))
      (node (ref "P2") (pin "10") (pinfunction "10_10") (pintype "unspecified"))
    )
    (net (code "9") (name "MAP") (class "Default")
      (node (ref "P1") (pin "13") (pinfunction "13_13") (pintype "unspecified"))
      (node (ref "P2") (pin "13") (pinfunction "13_13") (pintype "unspecified"))
    )
    (net (code "10") (name "Net-(C5-Pad2)") (class "Default")
      (node (ref "C5") (pin "2") (pinfunction "2_2") (pintype "unspecified"))
      (node (ref "R4") (pin "1") (pinfunction "1_1") (pintype "unspecified"))
      (node (ref "R5") (pin "2") (pinfunction "2_2") (pintype "unspecified"))
      (node (ref "R6") (pin "2") (pinfunction "2_2") (pintype "unspecified"))
    )
    (net (code "11") (name "Net-(D2-C)") (class "Default")
      (node (ref "D2") (pin "1") (pinfunction "C_1") (pintype "unspecified"))
      (node (ref "U1") (pin "1") (pinfunction "VIN_1") (pintype "unspecified"))
    )
    (net (code "12") (name "Net-(D3-A)") (class "Default")
      (node (ref "D3") (pin "2") (pinfunction "A_2") (pintype "unspecified"))
      (node (ref "LED1") (pin "2") (pinfunction "2_2") (pintype "unspecified"))
    )
    (net (code "13") (name "Net-(D4-A)") (class "Default")
      (node (ref "D4") (pin "2") (pinfunction "A_2") (pintype "unspecified"))
      (node (ref "LED2") (pin "2") (pinfunction "2_2") (pintype "unspecified"))
    )
    (net (code "14") (name "Net-(LED1-Pad1)") (class "Default")
      (node (ref "LED1") (pin "1") (pinfunction "1_1") (pintype "unspecified"))
      (node (ref "R1") (pin "2") (pinfunction "2_2") (pintype "unspecified"))
    )
    (net (code "15") (name "Net-(LED2-Pad1)") (class "Default")
      (node (ref "LED2") (pin "1") (pinfunction "1_1") (pintype "unspecified"))
      (node (ref "R8") (pin "2") (pinfunction "2_2") (pintype "unspecified"))
    )
    (net (code "16") (name "Net-(LED3-Pad1)") (class "Default")
      (node (ref "LED3") (pin "1") (pinfunction "1_1") (pintype "unspecified"))
      (node (ref "R11") (pin "2") (pinfunction "2_2") (pintype "unspecified"))
    )
    (net (code "17") (name "Net-(M1-G)") (class "Default")
      (node (ref "M1") (pin "1") (pinfunction "G_1") (pintype "unspecified"))
      (node (ref "R2") (pin "2") (pinfunction "2_2") (pintype "unspecified"))
    )
    (net (code "18") (name "Net-(M2-G)") (class "Default")
      (node (ref "M2") (pin "1") (pinfunction "G_1") (pintype "unspecified"))
      (node (ref "R9") (pin "2") (pinfunction "2_2") (pintype "unspecified"))
    )
    (net (code "19") (name "O2 Sensor") (class "Default")
      (node (ref "C7") (pin "2") (pinfunction "2_2") (pintype "unspecified"))
      (node (ref "R7") (pin "2") (pinfunction "2_2") (pintype "unspecified"))
    )
    (net (code "20") (name "O2-CPU") (class "Default")
      (node (ref "C8") (pin "2") (pinfunction "2_2") (pintype "unspecified"))
      (node (ref "P1") (pin "7") (pinfunction "7_7") (pintype "unspecified"))
      (node (ref "R7") (pin "1") (pinfunction "1_1") (pintype "unspecified"))
    )
    (net (code "21") (name "O2SENSOR") (class "Default")
      (node (ref "P2") (pin "7") (pinfunction "7_7") (pintype "unspecified"))
    )
    (net (code "22") (name "OIL Sensor") (class "Default")
      (node (ref "P1") (pin "14") (pinfunction "14_14") (pintype "unspecified"))
      (node (ref "P2") (pin "14") (pinfunction "14_14") (pintype "unspecified"))
    )
    (net (code "23") (name "PLUG1-CPU") (class "Default")
      (node (ref "P1") (pin "2") (pinfunction "2_2") (pintype "unspecified"))
      (node (ref "R10") (pin "2") (pinfunction "2_2") (pintype "unspecified"))
      (node (ref "R9") (pin "1") (pinfunction "1_1") (pintype "unspecified"))
    )
    (net (code "24") (name "STEPER-CPU1") (class "Default")
      (node (ref "P1") (pin "3") (pinfunction "3_3") (pintype "unspecified"))
    )
    (net (code "25") (name "STEPER-CPU2") (class "Default")
      (node (ref "P1") (pin "5") (pinfunction "5_5") (pintype "unspecified"))
    )
    (net (code "26") (name "STEPER-CPU3") (class "Default")
      (node (ref "P1") (pin "4") (pinfunction "4_4") (pintype "unspecified"))
    )
    (net (code "27") (name "STEPER-CPU4") (class "Default")
      (node (ref "P1") (pin "6") (pinfunction "6_6") (pintype "unspecified"))
    )
    (net (code "28") (name "STEPER1") (class "Default")
      (node (ref "P2") (pin "3") (pinfunction "3_3") (pintype "unspecified"))
    )
    (net (code "29") (name "STEPER2") (class "Default")
      (node (ref "P2") (pin "5") (pinfunction "5_5") (pintype "unspecified"))
    )
    (net (code "30") (name "STEPER3") (class "Default")
      (node (ref "P2") (pin "4") (pinfunction "4_4") (pintype "unspecified"))
    )
    (net (code "31") (name "STEPER4") (class "Default")
      (node (ref "P2") (pin "6") (pinfunction "6_6") (pintype "unspecified"))
    )
    (net (code "32") (name "Spark") (class "Default")
      (node (ref "P1") (pin "16") (pinfunction "16_16") (pintype "unspecified"))
      (node (ref "P2") (pin "16") (pinfunction "16_16") (pintype "unspecified"))
    )
    (net (code "33") (name "Steper-CPU1") (class "Default")
      (node (ref "U2") (pin "2") (pinfunction "INPUT1_2") (pintype "unspecified"))
    )
    (net (code "34") (name "Steper-CPU2") (class "Default")
      (node (ref "U2") (pin "7") (pinfunction "INPUT2_7") (pintype "unspecified"))
    )
    (net (code "35") (name "Steper-CPU3") (class "Default")
      (node (ref "U2") (pin "15") (pinfunction "INPUT4_15") (pintype "unspecified"))
    )
    (net (code "36") (name "Steper-CPU4") (class "Default")
      (node (ref "U2") (pin "10") (pinfunction "INPUT3_10") (pintype "unspecified"))
    )
    (net (code "37") (name "Steper1") (class "Default")
      (node (ref "U2") (pin "3") (pinfunction "OUTPUT1_3") (pintype "unspecified"))
    )
    (net (code "38") (name "Steper2") (class "Default")
      (node (ref "U2") (pin "6") (pinfunction "OUTPUT2_6") (pintype "unspecified"))
    )
    (net (code "39") (name "Steper3") (class "Default")
      (node (ref "U2") (pin "14") (pinfunction "OUTPUT4_14") (pintype "unspecified"))
    )
    (net (code "40") (name "Steper4") (class "Default")
      (node (ref "U2") (pin "11") (pinfunction "OUTPUT3_11") (pintype "unspecified"))
    )
    (net (code "41") (name "TEMP") (class "Default")
      (node (ref "P1") (pin "18") (pinfunction "18_18") (pintype "unspecified"))
      (node (ref "P2") (pin "18") (pinfunction "18_18") (pintype "unspecified"))
    )
    (net (code "42") (name "TPS") (class "Default")
      (node (ref "P1") (pin "12") (pinfunction "12_12") (pintype "unspecified"))
      (node (ref "P2") (pin "12") (pinfunction "12_12") (pintype "unspecified"))
    )
    (net (code "43") (name "VCC") (class "Default")
      (node (ref "C1") (pin "1") (pinfunction "1_1") (pintype "unspecified"))
      (node (ref "C2") (pin "1") (pinfunction "1_1") (pintype "unspecified"))
      (node (ref "D2") (pin "2") (pinfunction "A_2") (pintype "unspecified"))
      (node (ref "DC1") (pin "1") (pinfunction "1_1") (pintype "unspecified"))
      (node (ref "P2") (pin "1") (pinfunction "1_1") (pintype "unspecified"))
      (node (ref "R1") (pin "1") (pinfunction "1_1") (pintype "unspecified"))
      (node (ref "R4") (pin "2") (pinfunction "2_2") (pintype "unspecified"))
      (node (ref "R8") (pin "1") (pinfunction "1_1") (pintype "unspecified"))
      (node (ref "U2") (pin "8") (pinfunction "VS_8") (pintype "unspecified"))
      (node (ref "U4") (pin "1") (pinfunction "1_1") (pintype "unspecified"))
      (node (ref "U5") (pin "1") (pinfunction "1_1") (pintype "unspecified"))
    )
  )
)
